# lononTV.net
KiCad netlist of a schematic drawn in Altium Designer
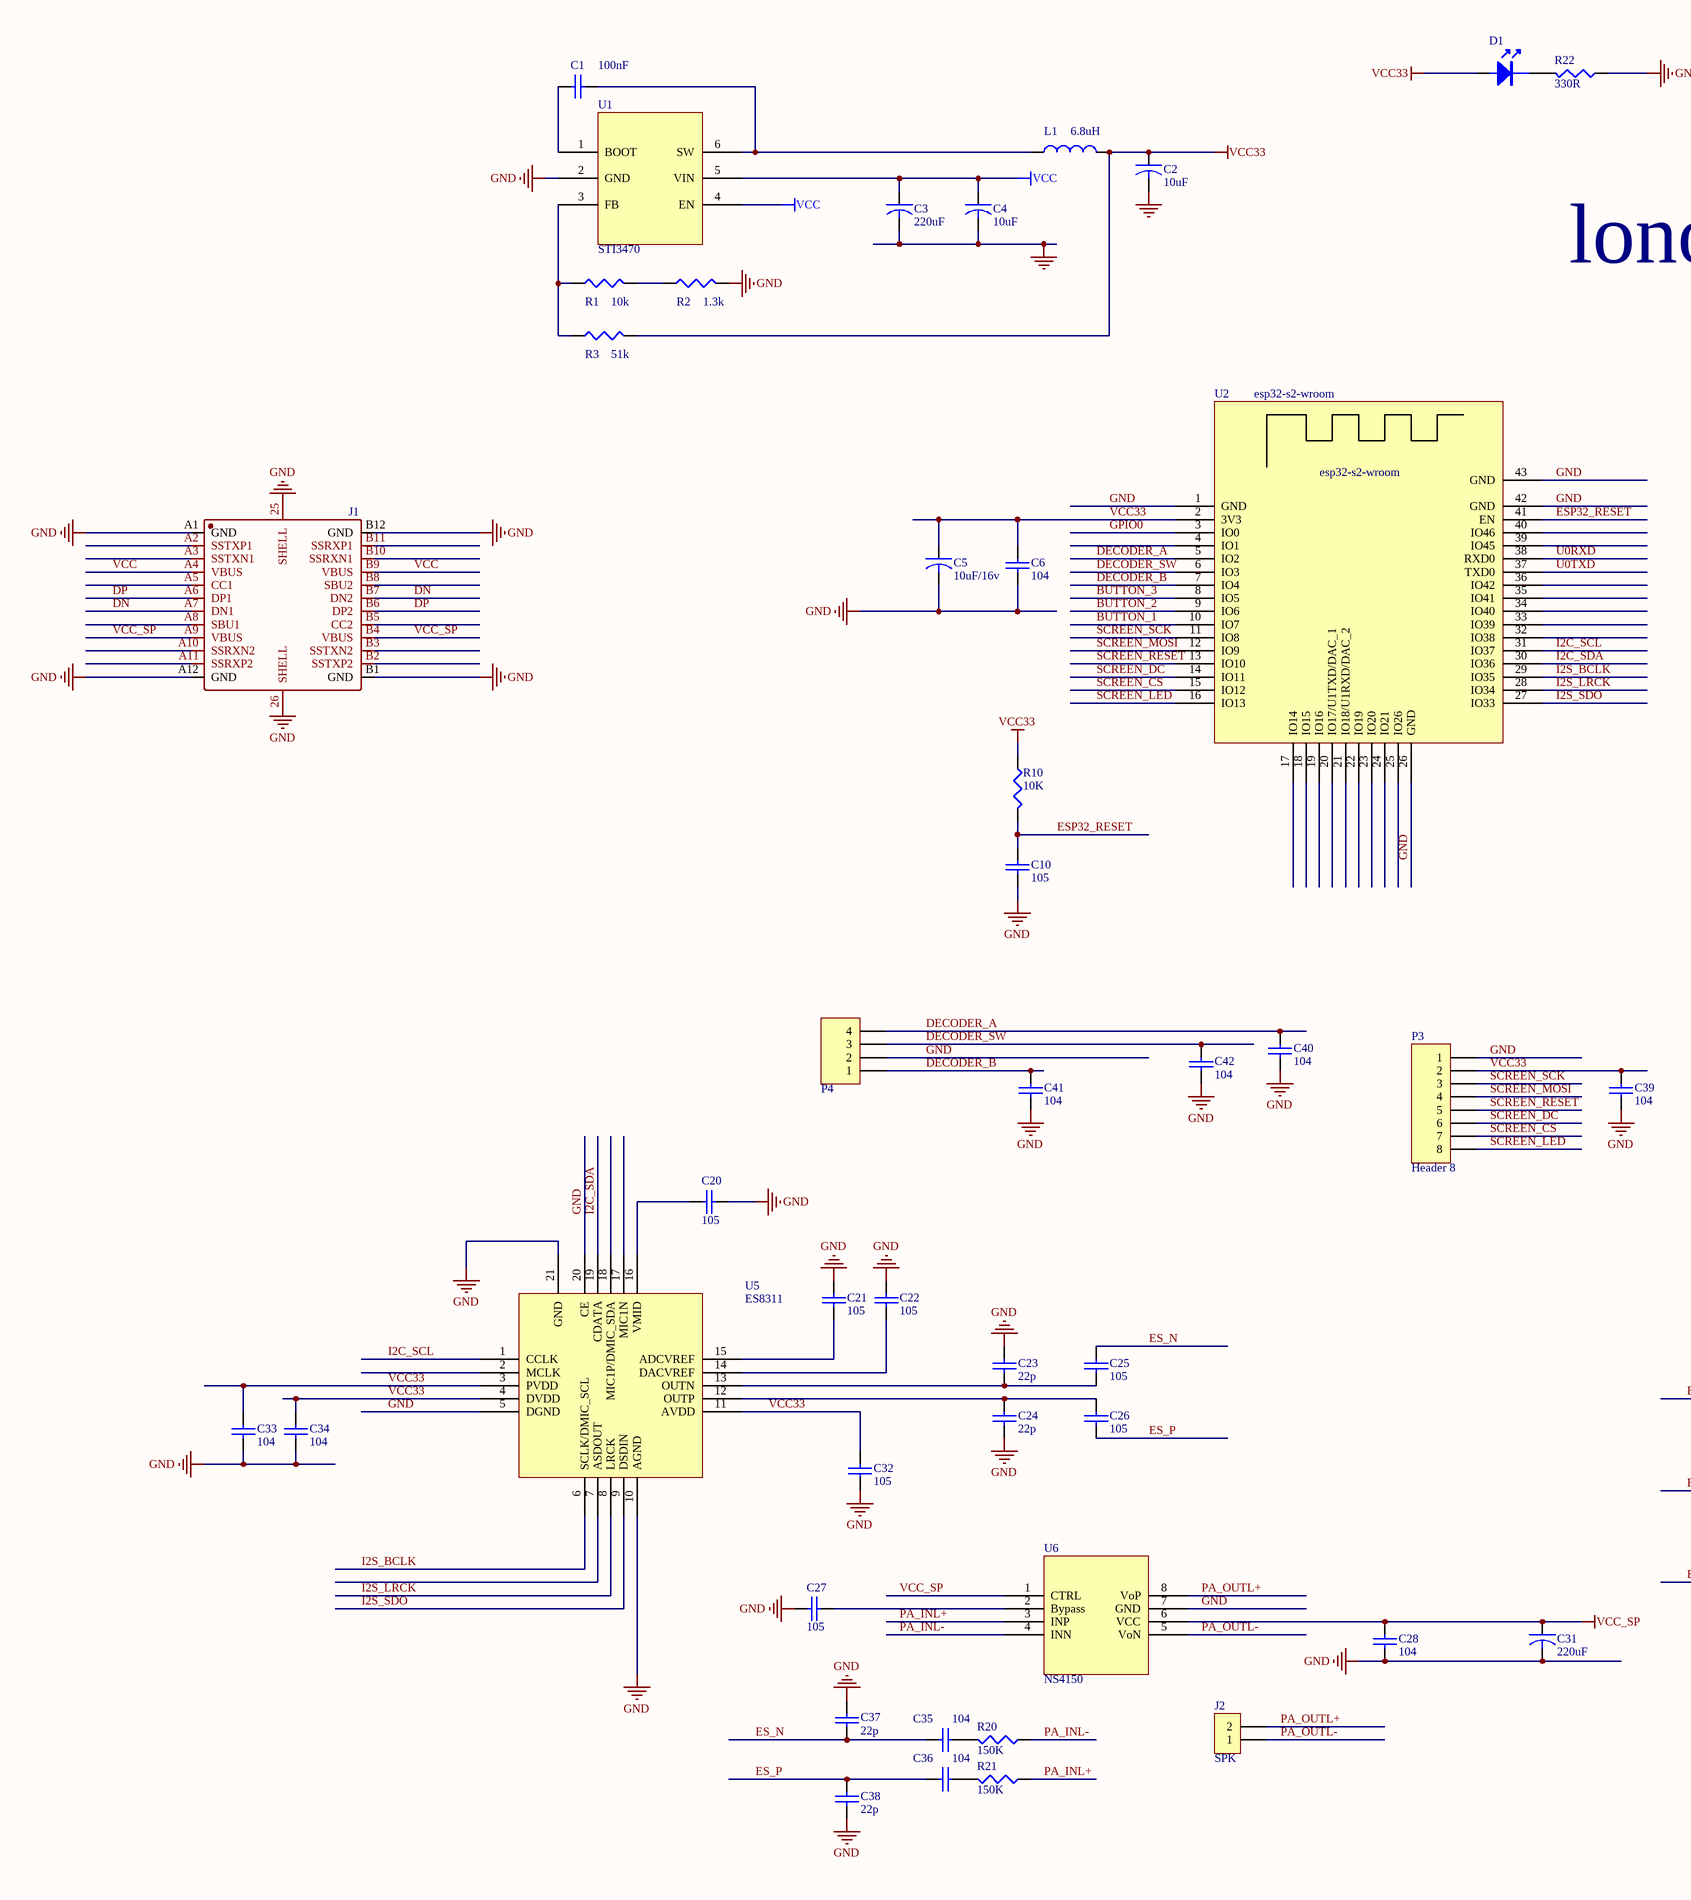
[diagram p0: lononTV.SchDoc, left]
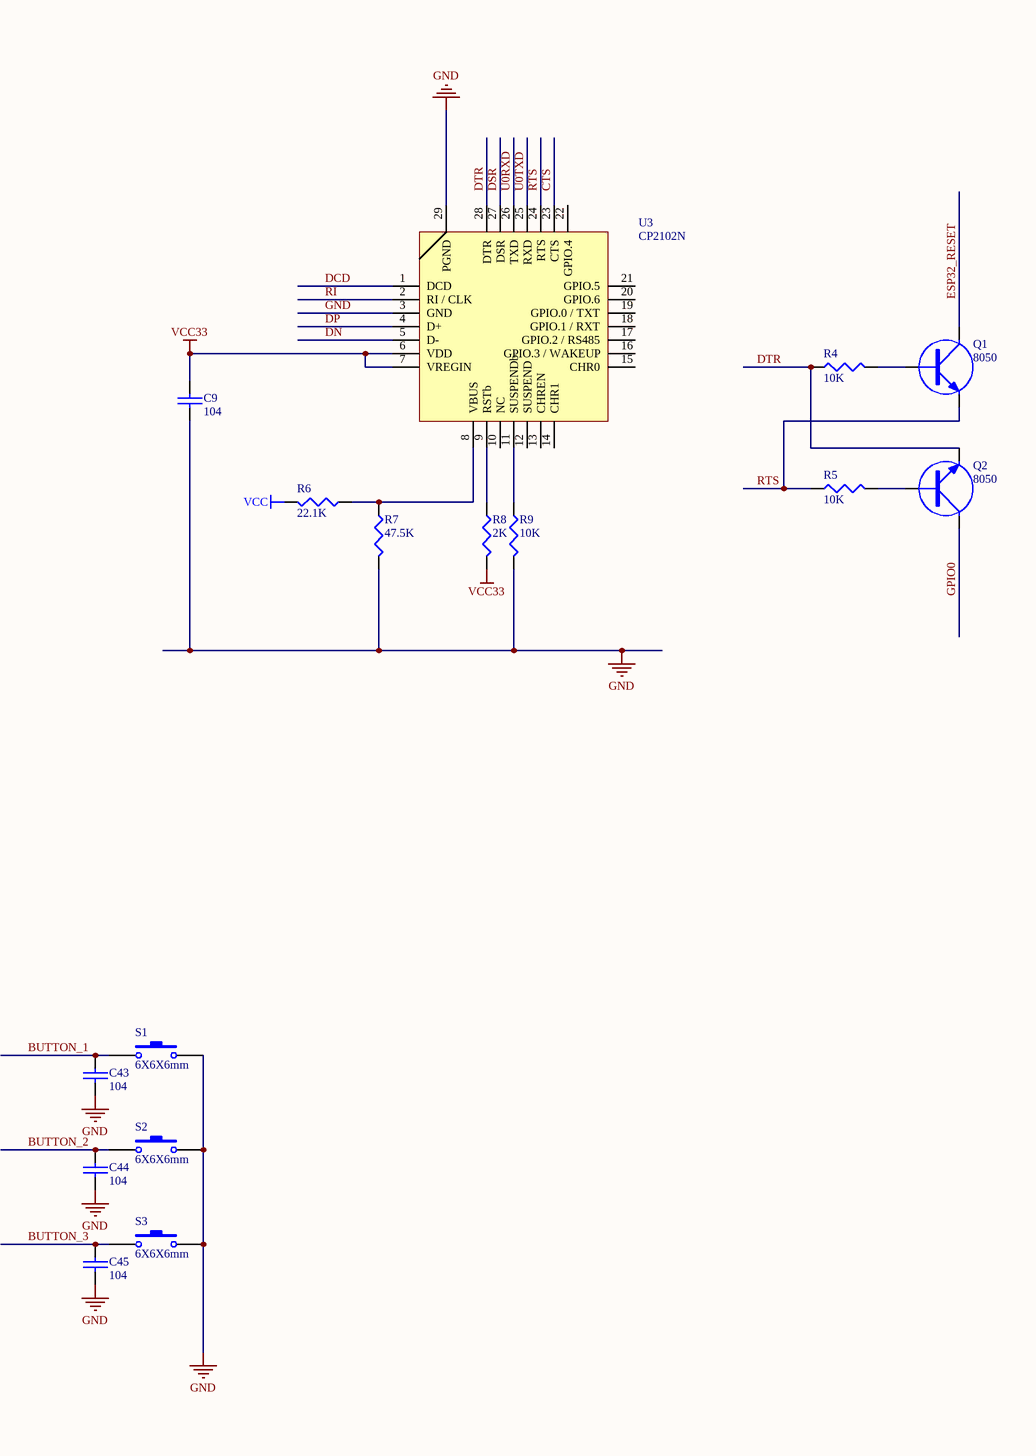
[diagram p1: lononTV.SchDoc, right]

(export (version "E")
  (design (tool "Eeschema 10.0.6"))
  (components
    (comp (ref "C1")
      (value "100nF")
      (footprint "0603C")
      (description "贴片电容")
      (libsource (lib "*") (part "CAP"))
    )
    (comp (ref "C2")
      (value "10uF")
      (footprint "1206-A")
      (description "钽电容")
      (libsource (lib "*") (part "CAPACITOR"))
    )
    (comp (ref "C3")
      (value "220uF")
      (footprint "铝电容6.6")
      (description "钽电容")
      (libsource (lib "*") (part "CAPACITOR"))
    )
    (comp (ref "C4")
      (value "10uF")
      (footprint "1206-A")
      (description "钽电容")
      (libsource (lib "*") (part "CAPACITOR"))
    )
    (comp (ref "C5")
      (value "10uF/16v")
      (footprint "1206-A")
      (description "Capacitor")
      (libsource (lib "zhjrm") (part "CAPACITOR"))
    )
    (comp (ref "C6")
      (value "104")
      (footprint "C0603 - duplicate")
      (description "Capacitor")
      (libsource (lib "zhjrm") (part "CAP"))
    )
    (comp (ref "C9")
      (value "104")
      (footprint "C0603 - duplicate")
      (description "Capacitor")
      (libsource (lib "zhjrm") (part "CAP"))
    )
    (comp (ref "C10")
      (value "105")
      (footprint "C0603 - duplicate")
      (description "Capacitor")
      (libsource (lib "zhjrm") (part "CAP"))
    )
    (comp (ref "C20")
      (value "105")
      (footprint "C0603 - duplicate")
      (description "Capacitor")
      (libsource (lib "zhjrm") (part "CAP"))
    )
    (comp (ref "C21")
      (value "105")
      (footprint "C0603 - duplicate")
      (description "Capacitor")
      (libsource (lib "zhjrm") (part "CAP"))
    )
    (comp (ref "C22")
      (value "105")
      (footprint "C0603 - duplicate")
      (description "Capacitor")
      (libsource (lib "zhjrm") (part "CAP"))
    )
    (comp (ref "C23")
      (value "22p")
      (footprint "C0603 - duplicate")
      (description "Capacitor")
      (libsource (lib "zhjrm") (part "CAP"))
    )
    (comp (ref "C24")
      (value "22p")
      (footprint "C0603 - duplicate")
      (description "Capacitor")
      (libsource (lib "zhjrm") (part "CAP"))
    )
    (comp (ref "C25")
      (value "105")
      (footprint "C0603 - duplicate")
      (description "Capacitor")
      (libsource (lib "zhjrm") (part "CAP"))
    )
    (comp (ref "C26")
      (value "105")
      (footprint "C0603 - duplicate")
      (description "Capacitor")
      (libsource (lib "zhjrm") (part "CAP"))
    )
    (comp (ref "C27")
      (value "105")
      (footprint "C0603 - duplicate")
      (description "Capacitor")
      (libsource (lib "zhjrm") (part "CAP"))
    )
    (comp (ref "C28")
      (value "104")
      (footprint "C0603 - duplicate")
      (description "Capacitor")
      (libsource (lib "zhjrm") (part "CAP"))
    )
    (comp (ref "C31")
      (value "220uF")
      (footprint "铝电容6.6")
      (description "Capacitor")
      (libsource (lib "zhjrm") (part "CAPACITOR"))
    )
    (comp (ref "C32")
      (value "105")
      (footprint "C0603 - duplicate")
      (description "Capacitor")
      (libsource (lib "zhjrm") (part "CAP"))
    )
    (comp (ref "C33")
      (value "104")
      (footprint "C0603 - duplicate")
      (description "Capacitor")
      (libsource (lib "zhjrm") (part "CAP"))
    )
    (comp (ref "C34")
      (value "104")
      (footprint "C0603 - duplicate")
      (description "Capacitor")
      (libsource (lib "zhjrm") (part "CAP"))
    )
    (comp (ref "C35")
      (value "104")
      (footprint "C0603 - duplicate")
      (description "Capacitor")
      (libsource (lib "zhjrm") (part "CAP"))
    )
    (comp (ref "C36")
      (value "104")
      (footprint "C0603 - duplicate")
      (description "Capacitor")
      (libsource (lib "zhjrm") (part "CAP"))
    )
    (comp (ref "C37")
      (value "22p")
      (footprint "C0603 - duplicate")
      (description "Capacitor")
      (libsource (lib "zhjrm") (part "CAP"))
    )
    (comp (ref "C38")
      (value "22p")
      (footprint "C0603 - duplicate")
      (description "Capacitor")
      (libsource (lib "zhjrm") (part "CAP"))
    )
    (comp (ref "C39")
      (value "104")
      (footprint "C0603 - duplicate")
      (description "Capacitor")
      (libsource (lib "zhjrm") (part "CAP"))
    )
    (comp (ref "C40")
      (value "104")
      (footprint "C0603 - duplicate")
      (description "Capacitor")
      (libsource (lib "zhjrm") (part "CAP"))
    )
    (comp (ref "C41")
      (value "104")
      (footprint "C0603 - duplicate")
      (description "Capacitor")
      (libsource (lib "zhjrm") (part "CAP"))
    )
    (comp (ref "C42")
      (value "104")
      (footprint "C0603 - duplicate")
      (description "Capacitor")
      (libsource (lib "zhjrm") (part "CAP"))
    )
    (comp (ref "C43")
      (value "104")
      (footprint "C0603 - duplicate")
      (description "Capacitor")
      (libsource (lib "zhjrm") (part "CAP"))
    )
    (comp (ref "C44")
      (value "104")
      (footprint "C0603 - duplicate")
      (description "Capacitor")
      (libsource (lib "zhjrm") (part "CAP"))
    )
    (comp (ref "C45")
      (value "104")
      (footprint "C0603 - duplicate")
      (description "Capacitor")
      (libsource (lib "zhjrm") (part "CAP"))
    )
    (comp (ref "D1") (value "~") (footprint "d0805") (libsource (lib "zhjrm") (part "LED")))
    (comp (ref "J1")
      (value "~")
      (footprint "TYPE-C夹板C2856664")
      (libsource (lib "zhjrm") (part "TYPE-C夹板C2856664"))
    )
    (comp (ref "J2") (value "SPK") (footprint "MX1.25-2P 立") (libsource (lib "zhjrm") (part "CON2")))
    (comp (ref "L1")
      (value "6.8uH")
      (footprint "电感7.4*6.6")
      (description "Inductor")
      (fields
        (field (name "MANUFACTURER") "Generic Components")
        (field (name "PUBLISHER") "Altium Hobart Technology Centre")
      )
      (libsource (lib "zhjrm") (part "Inductor"))
    )
    (comp (ref "P3")
      (value "Header 8")
      (footprint "HDR1X8")
      (description "Header, 8-Pin")
      (fields (field (name "PUBLISHER") "Altium Limited"))
      (libsource (lib "Miscellaneous Connectors") (part "Header 8"))
    )
    (comp (ref "P4")
      (value "Header 4")
      (footprint "MX1.25-4P 立")
      (description "Header, 4-Pin")
      (fields (field (name "PUBLISHER") "Altium Limited"))
      (libsource (lib "Miscellaneous Connectors") (part "Header 4"))
    )
    (comp (ref "Q1")
      (value "8050")
      (footprint "3904")
      (description "NPN Transistor")
      (libsource (lib "zhjrm") (part "NPN"))
    )
    (comp (ref "Q2")
      (value "8050")
      (footprint "3904")
      (description "NPN Transistor")
      (libsource (lib "zhjrm") (part "NPN"))
    )
    (comp (ref "R1") (value "10k") (footprint "0603R") (libsource (lib "*") (part "RES1")))
    (comp (ref "R2") (value "1.3k") (footprint "0603R") (libsource (lib "*") (part "RES1")))
    (comp (ref "R3") (value "51k") (footprint "0603R") (libsource (lib "*") (part "RES1")))
    (comp (ref "R4") (value "10K") (footprint "R0603") (libsource (lib "zhjrm") (part "RES1")))
    (comp (ref "R5") (value "10K") (footprint "R0603") (libsource (lib "zhjrm") (part "RES1")))
    (comp (ref "R6") (value "22.1K") (footprint "R0603") (libsource (lib "zhjrm") (part "RES1")))
    (comp (ref "R7") (value "47.5K") (footprint "R0603") (libsource (lib "zhjrm") (part "RES1")))
    (comp (ref "R8") (value "2K") (footprint "R0603") (libsource (lib "zhjrm") (part "RES1")))
    (comp (ref "R9") (value "10K") (footprint "R0603") (libsource (lib "zhjrm") (part "RES1")))
    (comp (ref "R10") (value "10K") (footprint "0603R") (libsource (lib "zhjrm") (part "RES1")))
    (comp (ref "R20") (value "150K") (footprint "0603R") (libsource (lib "zhjrm") (part "RES1")))
    (comp (ref "R21") (value "150K") (footprint "0603R") (libsource (lib "zhjrm") (part "RES1")))
    (comp (ref "R22") (value "330R") (footprint "0603R") (libsource (lib "zhjrm") (part "RES1")))
    (comp (ref "S1")
      (value "6X6X6mm")
      (footprint "C400237_KT红轴")
      (description "Switch")
      (fields (field (name "PUBLISHER") "Altium Limited"))
      (libsource (lib "zhjrm") (part "SW-PB"))
    )
    (comp (ref "S2")
      (value "6X6X6mm")
      (footprint "C400237_KT红轴")
      (description "Switch")
      (fields (field (name "PUBLISHER") "Altium Limited"))
      (libsource (lib "zhjrm") (part "SW-PB"))
    )
    (comp (ref "S3")
      (value "6X6X6mm")
      (footprint "C400237_KT红轴")
      (description "Switch")
      (fields (field (name "PUBLISHER") "Altium Limited"))
      (libsource (lib "zhjrm") (part "SW-PB"))
    )
    (comp (ref "U1") (value "STI3470") (footprint "SOT-23-6L") (libsource (lib "zhjrm") (part "RT7285/A")))
    (comp (ref "U2")
      (value "esp32-s2-wroom")
      (footprint "ESP32-S2-WROOM")
      (libsource (lib "zhjrm") (part "esp32-s2-wroom"))
    )
    (comp (ref "U3")
      (value "CP2102N")
      (footprint "QFN 28-pin-05P")
      (libsource (lib "zhjrm") (part "CP2102N"))
    )
    (comp (ref "U5") (value "ES8311") (footprint "QFN20_3*3") (libsource (lib "zhjrm") (part "ES8311")))
    (comp (ref "U6") (value "NS4150") (footprint "MSOP8") (libsource (lib "zhjrm") (part "NS4150")))
  )
  (nets
    (net (code "1") (name "/BUTTON_1") (class "Default")
      (node (ref "C43") (pin "1") (pinfunction "1_1") (pintype "passive"))
      (node (ref "S1") (pin "1") (pinfunction "1_1") (pintype "passive"))
      (node (ref "U2") (pin "10") (pinfunction "IO7_10") (pintype "passive"))
    )
    (net (code "2") (name "/BUTTON_2") (class "Default")
      (node (ref "C44") (pin "1") (pinfunction "1_1") (pintype "passive"))
      (node (ref "S2") (pin "1") (pinfunction "1_1") (pintype "passive"))
      (node (ref "U2") (pin "9") (pinfunction "IO6_9") (pintype "passive"))
    )
    (net (code "3") (name "/BUTTON_3") (class "Default")
      (node (ref "C45") (pin "1") (pinfunction "1_1") (pintype "passive"))
      (node (ref "S3") (pin "1") (pinfunction "1_1") (pintype "passive"))
      (node (ref "U2") (pin "8") (pinfunction "IO5_8") (pintype "passive"))
    )
    (net (code "4") (name "/CTS") (class "Default")
      (node (ref "U3") (pin "23") (pinfunction "CTS_23") (pintype "passive"))
    )
    (net (code "5") (name "/DCD") (class "Default")
      (node (ref "U3") (pin "1") (pinfunction "DCD_1") (pintype "passive"))
    )
    (net (code "6") (name "/DECODER_A") (class "Default")
      (node (ref "C40") (pin "1") (pinfunction "1_1") (pintype "passive"))
      (node (ref "P4") (pin "4") (pinfunction "4_4") (pintype "passive"))
      (node (ref "U2") (pin "5") (pinfunction "IO2_5") (pintype "passive"))
    )
    (net (code "7") (name "/DECODER_B") (class "Default")
      (node (ref "C41") (pin "1") (pinfunction "1_1") (pintype "passive"))
      (node (ref "P4") (pin "1") (pinfunction "1_1") (pintype "passive"))
      (node (ref "U2") (pin "7") (pinfunction "IO4_7") (pintype "passive"))
    )
    (net (code "8") (name "/DECODER_SW") (class "Default")
      (node (ref "C42") (pin "1") (pinfunction "1_1") (pintype "passive"))
      (node (ref "P4") (pin "3") (pinfunction "3_3") (pintype "passive"))
      (node (ref "U2") (pin "6") (pinfunction "IO3_6") (pintype "passive"))
    )
    (net (code "9") (name "/DN") (class "Default")
      (node (ref "J1") (pin "A7") (pinfunction "DN1_A7") (pintype "passive"))
      (node (ref "J1") (pin "B7") (pinfunction "DN2_B7") (pintype "passive"))
      (node (ref "U3") (pin "5") (pinfunction "D-_5") (pintype "passive"))
    )
    (net (code "10") (name "/DP") (class "Default")
      (node (ref "J1") (pin "A6") (pinfunction "DP1_A6") (pintype "passive"))
      (node (ref "J1") (pin "B6") (pinfunction "DP2_B6") (pintype "passive"))
      (node (ref "U3") (pin "4") (pinfunction "D+_4") (pintype "passive"))
    )
    (net (code "11") (name "/DSR") (class "Default")
      (node (ref "U3") (pin "27") (pinfunction "DSR_27") (pintype "passive"))
    )
    (net (code "12") (name "/DTR") (class "Default")
      (node (ref "Q2") (pin "3") (pinfunction "E_3") (pintype "passive"))
      (node (ref "R4") (pin "1") (pinfunction "1_1") (pintype "passive"))
      (node (ref "U3") (pin "28") (pinfunction "DTR_28") (pintype "passive"))
    )
    (net (code "13") (name "/ESP32_RESET") (class "Default")
      (node (ref "C10") (pin "1") (pinfunction "1_1") (pintype "passive"))
      (node (ref "Q1") (pin "2") (pinfunction "C_2") (pintype "passive"))
      (node (ref "R10") (pin "2") (pinfunction "2_2") (pintype "passive"))
      (node (ref "U2") (pin "41") (pinfunction "EN_41") (pintype "passive"))
    )
    (net (code "14") (name "/ES_N") (class "Default")
      (node (ref "C25") (pin "1") (pinfunction "1_1") (pintype "passive"))
      (node (ref "C35") (pin "2") (pinfunction "2_2") (pintype "passive"))
      (node (ref "C37") (pin "2") (pinfunction "2_2") (pintype "passive"))
    )
    (net (code "15") (name "/ES_P") (class "Default")
      (node (ref "C26") (pin "2") (pinfunction "2_2") (pintype "passive"))
      (node (ref "C36") (pin "2") (pinfunction "2_2") (pintype "passive"))
      (node (ref "C38") (pin "1") (pinfunction "1_1") (pintype "passive"))
    )
    (net (code "16") (name "/GPIO0") (class "Default")
      (node (ref "Q2") (pin "2") (pinfunction "C_2") (pintype "passive"))
      (node (ref "U2") (pin "3") (pinfunction "IO0_3") (pintype "passive"))
    )
    (net (code "17") (name "/I2C_SCL") (class "Default")
      (node (ref "U2") (pin "31") (pinfunction "IO37_31") (pintype "passive"))
      (node (ref "U5") (pin "1") (pinfunction "CCLK_1") (pintype "passive"))
    )
    (net (code "18") (name "/I2C_SDA") (class "Default")
      (node (ref "U2") (pin "30") (pinfunction "IO36_30") (pintype "passive"))
      (node (ref "U5") (pin "19") (pinfunction "CDATA_19") (pintype "passive"))
    )
    (net (code "19") (name "/I2S_BCLK") (class "Default")
      (node (ref "U2") (pin "29") (pinfunction "IO35_29") (pintype "passive"))
      (node (ref "U5") (pin "6") (pinfunction "SCLK/DMIC_SCL_6") (pintype "passive"))
    )
    (net (code "20") (name "/I2S_LRCK") (class "Default")
      (node (ref "U2") (pin "28") (pinfunction "IO34_28") (pintype "passive"))
      (node (ref "U5") (pin "8") (pinfunction "LRCK_8") (pintype "passive"))
    )
    (net (code "21") (name "/I2S_SDO") (class "Default")
      (node (ref "U2") (pin "27") (pinfunction "IO33_27") (pintype "passive"))
      (node (ref "U5") (pin "9") (pinfunction "DSDIN_9") (pintype "passive"))
    )
    (net (code "22") (name "/PA_INL+") (class "Default")
      (node (ref "R21") (pin "1") (pinfunction "1_1") (pintype "passive"))
      (node (ref "U6") (pin "3") (pinfunction "INP_3") (pintype "passive"))
    )
    (net (code "23") (name "/PA_INL-") (class "Default")
      (node (ref "R20") (pin "1") (pinfunction "1_1") (pintype "passive"))
      (node (ref "U6") (pin "4") (pinfunction "INN_4") (pintype "passive"))
    )
    (net (code "24") (name "/PA_OUTL+") (class "Default")
      (node (ref "J2") (pin "2") (pinfunction "2_2") (pintype "passive"))
      (node (ref "U6") (pin "8") (pinfunction "VoP_8") (pintype "passive"))
    )
    (net (code "25") (name "/PA_OUTL-") (class "Default")
      (node (ref "J2") (pin "1") (pinfunction "1_1") (pintype "passive"))
      (node (ref "U6") (pin "5") (pinfunction "VoN_5") (pintype "passive"))
    )
    (net (code "26") (name "/RI") (class "Default")
      (node (ref "U3") (pin "2") (pinfunction "RI_/_CLK_2") (pintype "passive"))
    )
    (net (code "27") (name "/RTS") (class "Default")
      (node (ref "Q1") (pin "3") (pinfunction "E_3") (pintype "passive"))
      (node (ref "R5") (pin "1") (pinfunction "1_1") (pintype "passive"))
      (node (ref "U3") (pin "24") (pinfunction "RTS_24") (pintype "passive"))
    )
    (net (code "28") (name "/SCREEN_CS") (class "Default")
      (node (ref "P3") (pin "7") (pinfunction "7_7") (pintype "passive"))
      (node (ref "U2") (pin "15") (pinfunction "IO12_15") (pintype "passive"))
    )
    (net (code "29") (name "/SCREEN_DC") (class "Default")
      (node (ref "P3") (pin "6") (pinfunction "6_6") (pintype "passive"))
      (node (ref "U2") (pin "14") (pinfunction "IO11_14") (pintype "passive"))
    )
    (net (code "30") (name "/SCREEN_LED") (class "Default")
      (node (ref "P3") (pin "8") (pinfunction "8_8") (pintype "passive"))
      (node (ref "U2") (pin "16") (pinfunction "IO13_16") (pintype "passive"))
    )
    (net (code "31") (name "/SCREEN_MOSI") (class "Default")
      (node (ref "P3") (pin "4") (pinfunction "4_4") (pintype "passive"))
      (node (ref "U2") (pin "12") (pinfunction "IO9_12") (pintype "passive"))
    )
    (net (code "32") (name "/SCREEN_RESET") (class "Default")
      (node (ref "P3") (pin "5") (pinfunction "5_5") (pintype "passive"))
      (node (ref "U2") (pin "13") (pinfunction "IO10_13") (pintype "passive"))
    )
    (net (code "33") (name "/SCREEN_SCK") (class "Default")
      (node (ref "P3") (pin "3") (pinfunction "3_3") (pintype "passive"))
      (node (ref "U2") (pin "11") (pinfunction "IO8_11") (pintype "passive"))
    )
    (net (code "34") (name "/U0RXD") (class "Default")
      (node (ref "U2") (pin "38") (pinfunction "RXD0_38") (pintype "passive"))
      (node (ref "U3") (pin "26") (pinfunction "TXD_26") (pintype "passive"))
    )
    (net (code "35") (name "/U0TXD") (class "Default")
      (node (ref "U2") (pin "37") (pinfunction "TXD0_37") (pintype "passive"))
      (node (ref "U3") (pin "25") (pinfunction "RXD_25") (pintype "passive"))
    )
    (net (code "36") (name "GND") (class "Default")
      (node (ref "C10") (pin "2") (pinfunction "2_2") (pintype "passive"))
      (node (ref "C2") (pin "2") (pinfunction "2_2") (pintype "passive"))
      (node (ref "C20") (pin "2") (pinfunction "2_2") (pintype "passive"))
      (node (ref "C21") (pin "2") (pinfunction "2_2") (pintype "passive"))
      (node (ref "C22") (pin "2") (pinfunction "2_2") (pintype "passive"))
      (node (ref "C23") (pin "1") (pinfunction "1_1") (pintype "passive"))
      (node (ref "C24") (pin "2") (pinfunction "2_2") (pintype "passive"))
      (node (ref "C27") (pin "1") (pinfunction "1_1") (pintype "passive"))
      (node (ref "C28") (pin "1") (pinfunction "1_1") (pintype "passive"))
      (node (ref "C3") (pin "2") (pinfunction "2_2") (pintype "passive"))
      (node (ref "C31") (pin "2") (pinfunction "2_2") (pintype "passive"))
      (node (ref "C32") (pin "1") (pinfunction "1_1") (pintype "passive"))
      (node (ref "C33") (pin "1") (pinfunction "1_1") (pintype "passive"))
      (node (ref "C34") (pin "1") (pinfunction "1_1") (pintype "passive"))
      (node (ref "C37") (pin "1") (pinfunction "1_1") (pintype "passive"))
      (node (ref "C38") (pin "2") (pinfunction "2_2") (pintype "passive"))
      (node (ref "C39") (pin "2") (pinfunction "2_2") (pintype "passive"))
      (node (ref "C4") (pin "2") (pinfunction "2_2") (pintype "passive"))
      (node (ref "C40") (pin "2") (pinfunction "2_2") (pintype "passive"))
      (node (ref "C41") (pin "2") (pinfunction "2_2") (pintype "passive"))
      (node (ref "C42") (pin "2") (pinfunction "2_2") (pintype "passive"))
      (node (ref "C43") (pin "2") (pinfunction "2_2") (pintype "passive"))
      (node (ref "C44") (pin "2") (pinfunction "2_2") (pintype "passive"))
      (node (ref "C45") (pin "2") (pinfunction "2_2") (pintype "passive"))
      (node (ref "C5") (pin "2") (pinfunction "2_2") (pintype "passive"))
      (node (ref "C6") (pin "2") (pinfunction "2_2") (pintype "passive"))
      (node (ref "C9") (pin "2") (pinfunction "2_2") (pintype "passive"))
      (node (ref "J1") (pin "25") (pinfunction "SHELL_25") (pintype "passive"))
      (node (ref "J1") (pin "26") (pinfunction "SHELL_26") (pintype "passive"))
      (node (ref "J1") (pin "A1") (pinfunction "GND_A1") (pintype "passive"))
      (node (ref "J1") (pin "A12") (pinfunction "GND_A12") (pintype "passive"))
      (node (ref "J1") (pin "B1") (pinfunction "GND_B1") (pintype "passive"))
      (node (ref "J1") (pin "B12") (pinfunction "GND_B12") (pintype "passive"))
      (node (ref "P3") (pin "1") (pinfunction "1_1") (pintype "passive"))
      (node (ref "P4") (pin "2") (pinfunction "2_2") (pintype "passive"))
      (node (ref "R2") (pin "1") (pinfunction "1_1") (pintype "passive"))
      (node (ref "R22") (pin "1") (pinfunction "1_1") (pintype "passive"))
      (node (ref "R7") (pin "2") (pinfunction "2_2") (pintype "passive"))
      (node (ref "R9") (pin "2") (pinfunction "2_2") (pintype "passive"))
      (node (ref "S1") (pin "2") (pinfunction "2_2") (pintype "passive"))
      (node (ref "S2") (pin "2") (pinfunction "2_2") (pintype "passive"))
      (node (ref "S3") (pin "2") (pinfunction "2_2") (pintype "passive"))
      (node (ref "U1") (pin "2") (pinfunction "GND_2") (pintype "passive"))
      (node (ref "U2") (pin "1") (pinfunction "GND_1") (pintype "passive"))
      (node (ref "U2") (pin "26") (pinfunction "GND_26") (pintype "passive"))
      (node (ref "U2") (pin "42") (pinfunction "GND_42") (pintype "passive"))
      (node (ref "U2") (pin "43") (pinfunction "GND_43") (pintype "passive"))
      (node (ref "U3") (pin "29") (pinfunction "PGND_29") (pintype "passive"))
      (node (ref "U3") (pin "3") (pinfunction "GND_3") (pintype "passive"))
      (node (ref "U5") (pin "10") (pinfunction "AGND_10") (pintype "passive"))
      (node (ref "U5") (pin "20") (pinfunction "CE_20") (pintype "passive"))
      (node (ref "U5") (pin "21") (pinfunction "GND_21") (pintype "passive"))
      (node (ref "U5") (pin "5") (pinfunction "DGND_5") (pintype "passive"))
      (node (ref "U6") (pin "7") (pinfunction "GND_7") (pintype "passive"))
    )
    (net (code "37") (name "Net-(C35-Pad1)") (class "Default")
      (node (ref "C35") (pin "1") (pinfunction "1_1") (pintype "passive"))
      (node (ref "R20") (pin "2") (pinfunction "2_2") (pintype "passive"))
    )
    (net (code "38") (name "Net-(C36-Pad1)") (class "Default")
      (node (ref "C36") (pin "1") (pinfunction "1_1") (pintype "passive"))
      (node (ref "R21") (pin "2") (pinfunction "2_2") (pintype "passive"))
    )
    (net (code "39") (name "Net-(D1-2)") (class "Default")
      (node (ref "D1") (pin "K") (pinfunction "2_K") (pintype "passive"))
      (node (ref "R22") (pin "2") (pinfunction "2_2") (pintype "passive"))
    )
    (net (code "40") (name "Net-(Q1-B)") (class "Default")
      (node (ref "Q1") (pin "1") (pinfunction "B_1") (pintype "passive"))
      (node (ref "R4") (pin "2") (pinfunction "2_2") (pintype "passive"))
    )
    (net (code "41") (name "Net-(Q2-B)") (class "Default")
      (node (ref "Q2") (pin "1") (pinfunction "B_1") (pintype "passive"))
      (node (ref "R5") (pin "2") (pinfunction "2_2") (pintype "passive"))
    )
    (net (code "42") (name "Net-(R1-Pad1)") (class "Default")
      (node (ref "R1") (pin "1") (pinfunction "1_1") (pintype "passive"))
      (node (ref "R2") (pin "2") (pinfunction "2_2") (pintype "passive"))
    )
    (net (code "43") (name "Net-(U1-BOOT)") (class "Default")
      (node (ref "C1") (pin "1") (pinfunction "1_1") (pintype "passive"))
      (node (ref "U1") (pin "1") (pinfunction "BOOT_1") (pintype "passive"))
    )
    (net (code "44") (name "Net-(U1-FB)") (class "Default")
      (node (ref "R1") (pin "2") (pinfunction "2_2") (pintype "passive"))
      (node (ref "R3") (pin "2") (pinfunction "2_2") (pintype "passive"))
      (node (ref "U1") (pin "3") (pinfunction "FB_3") (pintype "passive"))
    )
    (net (code "45") (name "Net-(U1-SW)") (class "Default")
      (node (ref "C1") (pin "2") (pinfunction "2_2") (pintype "passive"))
      (node (ref "L1") (pin "1") (pinfunction "1_1") (pintype "passive"))
      (node (ref "U1") (pin "6") (pinfunction "SW_6") (pintype "passive"))
    )
    (net (code "46") (name "Net-(U3-RSTb)") (class "Default")
      (node (ref "R8") (pin "1") (pinfunction "1_1") (pintype "passive"))
      (node (ref "U3") (pin "9") (pinfunction "RSTb_9") (pintype "passive"))
    )
    (net (code "47") (name "Net-(U3-SUSPENDb)") (class "Default")
      (node (ref "R9") (pin "1") (pinfunction "1_1") (pintype "passive"))
      (node (ref "U3") (pin "11") (pinfunction "SUSPENDb_11") (pintype "passive"))
    )
    (net (code "48") (name "Net-(U3-VBUS)") (class "Default")
      (node (ref "R6") (pin "1") (pinfunction "1_1") (pintype "passive"))
      (node (ref "R7") (pin "1") (pinfunction "1_1") (pintype "passive"))
      (node (ref "U3") (pin "8") (pinfunction "VBUS_8") (pintype "passive"))
    )
    (net (code "49") (name "Net-(U5-ADCVREF)") (class "Default")
      (node (ref "C21") (pin "1") (pinfunction "1_1") (pintype "passive"))
      (node (ref "U5") (pin "15") (pinfunction "ADCVREF_15") (pintype "passive"))
    )
    (net (code "50") (name "Net-(U5-DACVREF)") (class "Default")
      (node (ref "C22") (pin "1") (pinfunction "1_1") (pintype "passive"))
      (node (ref "U5") (pin "14") (pinfunction "DACVREF_14") (pintype "passive"))
    )
    (net (code "51") (name "Net-(U5-OUTN)") (class "Default")
      (node (ref "C23") (pin "2") (pinfunction "2_2") (pintype "passive"))
      (node (ref "C25") (pin "2") (pinfunction "2_2") (pintype "passive"))
      (node (ref "U5") (pin "13") (pinfunction "OUTN_13") (pintype "passive"))
    )
    (net (code "52") (name "Net-(U5-OUTP)") (class "Default")
      (node (ref "C24") (pin "1") (pinfunction "1_1") (pintype "passive"))
      (node (ref "C26") (pin "1") (pinfunction "1_1") (pintype "passive"))
      (node (ref "U5") (pin "12") (pinfunction "OUTP_12") (pintype "passive"))
    )
    (net (code "53") (name "Net-(U5-VMID)") (class "Default")
      (node (ref "C20") (pin "1") (pinfunction "1_1") (pintype "passive"))
      (node (ref "U5") (pin "16") (pinfunction "VMID_16") (pintype "passive"))
    )
    (net (code "54") (name "Net-(U6-Bypass)") (class "Default")
      (node (ref "C27") (pin "2") (pinfunction "2_2") (pintype "passive"))
      (node (ref "U6") (pin "2") (pinfunction "Bypass_2") (pintype "passive"))
    )
    (net (code "55") (name "VCC") (class "Default")
      (node (ref "C3") (pin "1") (pinfunction "1_1") (pintype "passive"))
      (node (ref "C4") (pin "1") (pinfunction "1_1") (pintype "passive"))
      (node (ref "J1") (pin "A4") (pinfunction "VBUS_A4") (pintype "passive"))
      (node (ref "J1") (pin "B9") (pinfunction "VBUS_B9") (pintype "passive"))
      (node (ref "R6") (pin "2") (pinfunction "2_2") (pintype "passive"))
      (node (ref "U1") (pin "4") (pinfunction "EN_4") (pintype "passive"))
      (node (ref "U1") (pin "5") (pinfunction "VIN_5") (pintype "passive"))
    )
    (net (code "56") (name "VCC33") (class "Default")
      (node (ref "C2") (pin "1") (pinfunction "1_1") (pintype "passive"))
      (node (ref "C32") (pin "2") (pinfunction "2_2") (pintype "passive"))
      (node (ref "C33") (pin "2") (pinfunction "2_2") (pintype "passive"))
      (node (ref "C34") (pin "2") (pinfunction "2_2") (pintype "passive"))
      (node (ref "C39") (pin "1") (pinfunction "1_1") (pintype "passive"))
      (node (ref "C5") (pin "1") (pinfunction "1_1") (pintype "passive"))
      (node (ref "C6") (pin "1") (pinfunction "1_1") (pintype "passive"))
      (node (ref "C9") (pin "1") (pinfunction "1_1") (pintype "passive"))
      (node (ref "D1") (pin "A") (pinfunction "1_A") (pintype "passive"))
      (node (ref "L1") (pin "2") (pinfunction "2_2") (pintype "passive"))
      (node (ref "P3") (pin "2") (pinfunction "2_2") (pintype "passive"))
      (node (ref "R10") (pin "1") (pinfunction "1_1") (pintype "passive"))
      (node (ref "R3") (pin "1") (pinfunction "1_1") (pintype "passive"))
      (node (ref "R8") (pin "2") (pinfunction "2_2") (pintype "passive"))
      (node (ref "U2") (pin "2") (pinfunction "3V3_2") (pintype "passive"))
      (node (ref "U3") (pin "6") (pinfunction "VDD_6") (pintype "passive"))
      (node (ref "U3") (pin "7") (pinfunction "VREGIN_7") (pintype "passive"))
      (node (ref "U5") (pin "11") (pinfunction "AVDD_11") (pintype "passive"))
      (node (ref "U5") (pin "3") (pinfunction "PVDD_3") (pintype "passive"))
      (node (ref "U5") (pin "4") (pinfunction "DVDD_4") (pintype "passive"))
    )
    (net (code "57") (name "VCC_SP") (class "Default")
      (node (ref "C28") (pin "2") (pinfunction "2_2") (pintype "passive"))
      (node (ref "C31") (pin "1") (pinfunction "1_1") (pintype "passive"))
      (node (ref "J1") (pin "A9") (pinfunction "VBUS_A9") (pintype "passive"))
      (node (ref "J1") (pin "B4") (pinfunction "VBUS_B4") (pintype "passive"))
      (node (ref "U6") (pin "1") (pinfunction "CTRL_1") (pintype "passive"))
      (node (ref "U6") (pin "6") (pinfunction "VCC_6") (pintype "passive"))
    )
    (net (code "58") (name "unconnected-(J1-CC1-PadA5)") (class "Default")
      (node (ref "J1") (pin "A5") (pinfunction "CC1_A5") (pintype "passive"))
    )
    (net (code "59") (name "unconnected-(J1-CC2-PadB5)") (class "Default")
      (node (ref "J1") (pin "B5") (pinfunction "CC2_B5") (pintype "passive"))
    )
    (net (code "60") (name "unconnected-(J1-SBU1-PadA8)") (class "Default")
      (node (ref "J1") (pin "A8") (pinfunction "SBU1_A8") (pintype "passive"))
    )
    (net (code "61") (name "unconnected-(J1-SBU2-PadB8)") (class "Default")
      (node (ref "J1") (pin "B8") (pinfunction "SBU2_B8") (pintype "passive"))
    )
    (net (code "62") (name "unconnected-(J1-SSRXN1-PadB10)") (class "Default")
      (node (ref "J1") (pin "B10") (pinfunction "SSRXN1_B10") (pintype "passive"))
    )
    (net (code "63") (name "unconnected-(J1-SSRXN2-PadA10)") (class "Default")
      (node (ref "J1") (pin "A10") (pinfunction "SSRXN2_A10") (pintype "passive"))
    )
    (net (code "64") (name "unconnected-(J1-SSRXP1-PadB11)") (class "Default")
      (node (ref "J1") (pin "B11") (pinfunction "SSRXP1_B11") (pintype "passive"))
    )
    (net (code "65") (name "unconnected-(J1-SSRXP2-PadA11)") (class "Default")
      (node (ref "J1") (pin "A11") (pinfunction "SSRXP2_A11") (pintype "passive"))
    )
    (net (code "66") (name "unconnected-(J1-SSTXN1-PadA3)") (class "Default")
      (node (ref "J1") (pin "A3") (pinfunction "SSTXN1_A3") (pintype "passive"))
    )
    (net (code "67") (name "unconnected-(J1-SSTXN2-PadB3)") (class "Default")
      (node (ref "J1") (pin "B3") (pinfunction "SSTXN2_B3") (pintype "passive"))
    )
    (net (code "68") (name "unconnected-(J1-SSTXP1-PadA2)") (class "Default")
      (node (ref "J1") (pin "A2") (pinfunction "SSTXP1_A2") (pintype "passive"))
    )
    (net (code "69") (name "unconnected-(J1-SSTXP2-PadB2)") (class "Default")
      (node (ref "J1") (pin "B2") (pinfunction "SSTXP2_B2") (pintype "passive"))
    )
    (net (code "70") (name "unconnected-(U2-IO1-Pad4)") (class "Default")
      (node (ref "U2") (pin "4") (pinfunction "IO1_4") (pintype "passive"))
    )
    (net (code "71") (name "unconnected-(U2-IO14-Pad17)") (class "Default")
      (node (ref "U2") (pin "17") (pinfunction "IO14_17") (pintype "passive"))
    )
    (net (code "72") (name "unconnected-(U2-IO15-Pad18)") (class "Default")
      (node (ref "U2") (pin "18") (pinfunction "IO15_18") (pintype "passive"))
    )
    (net (code "73") (name "unconnected-(U2-IO16-Pad19)") (class "Default")
      (node (ref "U2") (pin "19") (pinfunction "IO16_19") (pintype "passive"))
    )
    (net (code "74") (name "unconnected-(U2-IO17{slash}U1TXD{slash}DAC_1-Pad20)") (class "Default")
      (node (ref "U2") (pin "20") (pinfunction "IO17/U1TXD/DAC_1_20") (pintype "passive"))
    )
    (net (code "75") (name "unconnected-(U2-IO18{slash}U1RXD{slash}DAC_2-Pad21)") (class "Default")
      (node (ref "U2") (pin "21") (pinfunction "IO18/U1RXD/DAC_2_21") (pintype "passive"))
    )
    (net (code "76") (name "unconnected-(U2-IO19-Pad22)") (class "Default")
      (node (ref "U2") (pin "22") (pinfunction "IO19_22") (pintype "passive"))
    )
    (net (code "77") (name "unconnected-(U2-IO20-Pad23)") (class "Default")
      (node (ref "U2") (pin "23") (pinfunction "IO20_23") (pintype "passive"))
    )
    (net (code "78") (name "unconnected-(U2-IO21-Pad24)") (class "Default")
      (node (ref "U2") (pin "24") (pinfunction "IO21_24") (pintype "passive"))
    )
    (net (code "79") (name "unconnected-(U2-IO26-Pad25)") (class "Default")
      (node (ref "U2") (pin "25") (pinfunction "IO26_25") (pintype "passive"))
    )
    (net (code "80") (name "unconnected-(U2-IO38-Pad32)") (class "Default")
      (node (ref "U2") (pin "32") (pinfunction "IO38_32") (pintype "passive"))
    )
    (net (code "81") (name "unconnected-(U2-IO39-Pad33)") (class "Default")
      (node (ref "U2") (pin "33") (pinfunction "IO39_33") (pintype "passive"))
    )
    (net (code "82") (name "unconnected-(U2-IO40-Pad34)") (class "Default")
      (node (ref "U2") (pin "34") (pinfunction "IO40_34") (pintype "passive"))
    )
    (net (code "83") (name "unconnected-(U2-IO41-Pad35)") (class "Default")
      (node (ref "U2") (pin "35") (pinfunction "IO41_35") (pintype "passive"))
    )
    (net (code "84") (name "unconnected-(U2-IO42-Pad36)") (class "Default")
      (node (ref "U2") (pin "36") (pinfunction "IO42_36") (pintype "passive"))
    )
    (net (code "85") (name "unconnected-(U2-IO45-Pad39)") (class "Default")
      (node (ref "U2") (pin "39") (pinfunction "IO45_39") (pintype "passive"))
    )
    (net (code "86") (name "unconnected-(U2-IO46-Pad40)") (class "Default")
      (node (ref "U2") (pin "40") (pinfunction "IO46_40") (pintype "passive"))
    )
    (net (code "87") (name "unconnected-(U3-CHR0-Pad15)") (class "Default")
      (node (ref "U3") (pin "15") (pinfunction "CHR0_15") (pintype "passive"))
    )
    (net (code "88") (name "unconnected-(U3-CHR1-Pad14)") (class "Default")
      (node (ref "U3") (pin "14") (pinfunction "CHR1_14") (pintype "passive"))
    )
    (net (code "89") (name "unconnected-(U3-CHREN-Pad13)") (class "Default")
      (node (ref "U3") (pin "13") (pinfunction "CHREN_13") (pintype "passive"))
    )
    (net (code "90") (name "unconnected-(U3-GPIO.0_{slash}_TXT-Pad19)") (class "Default")
      (node (ref "U3") (pin "19") (pinfunction "GPIO.0_/_TXT_19") (pintype "passive"))
    )
    (net (code "91") (name "unconnected-(U3-GPIO.1_{slash}_RXT-Pad18)") (class "Default")
      (node (ref "U3") (pin "18") (pinfunction "GPIO.1_/_RXT_18") (pintype "passive"))
    )
    (net (code "92") (name "unconnected-(U3-GPIO.2_{slash}_RS485-Pad17)") (class "Default")
      (node (ref "U3") (pin "17") (pinfunction "GPIO.2_/_RS485_17") (pintype "passive"))
    )
    (net (code "93") (name "unconnected-(U3-GPIO.3_{slash}_WAKEUP-Pad16)") (class "Default")
      (node (ref "U3") (pin "16") (pinfunction "GPIO.3_/_WAKEUP_16") (pintype "passive"))
    )
    (net (code "94") (name "unconnected-(U3-GPIO.4-Pad22)") (class "Default")
      (node (ref "U3") (pin "22") (pinfunction "GPIO.4_22") (pintype "passive"))
    )
    (net (code "95") (name "unconnected-(U3-GPIO.5-Pad21)") (class "Default")
      (node (ref "U3") (pin "21") (pinfunction "GPIO.5_21") (pintype "passive"))
    )
    (net (code "96") (name "unconnected-(U3-GPIO.6-Pad20)") (class "Default")
      (node (ref "U3") (pin "20") (pinfunction "GPIO.6_20") (pintype "passive"))
    )
    (net (code "97") (name "unconnected-(U3-NC-Pad10)") (class "Default")
      (node (ref "U3") (pin "10") (pinfunction "NC_10") (pintype "passive"))
    )
    (net (code "98") (name "unconnected-(U3-SUSPEND-Pad12)") (class "Default")
      (node (ref "U3") (pin "12") (pinfunction "SUSPEND_12") (pintype "passive"))
    )
    (net (code "99") (name "unconnected-(U5-ASDOUT-Pad7)") (class "Default")
      (node (ref "U5") (pin "7") (pinfunction "ASDOUT_7") (pintype "passive"))
    )
    (net (code "100") (name "unconnected-(U5-MCLK-Pad2)") (class "Default")
      (node (ref "U5") (pin "2") (pinfunction "MCLK_2") (pintype "passive"))
    )
    (net (code "101") (name "unconnected-(U5-MIC1N-Pad17)") (class "Default")
      (node (ref "U5") (pin "17") (pinfunction "MIC1N_17") (pintype "passive"))
    )
    (net (code "102") (name "unconnected-(U5-MIC1P{slash}DMIC_SDA-Pad18)") (class "Default")
      (node (ref "U5") (pin "18") (pinfunction "MIC1P/DMIC_SDA_18") (pintype "passive"))
    )
  )
)
